# CONN.net
KiCad netlist of a schematic drawn in Altium Designer
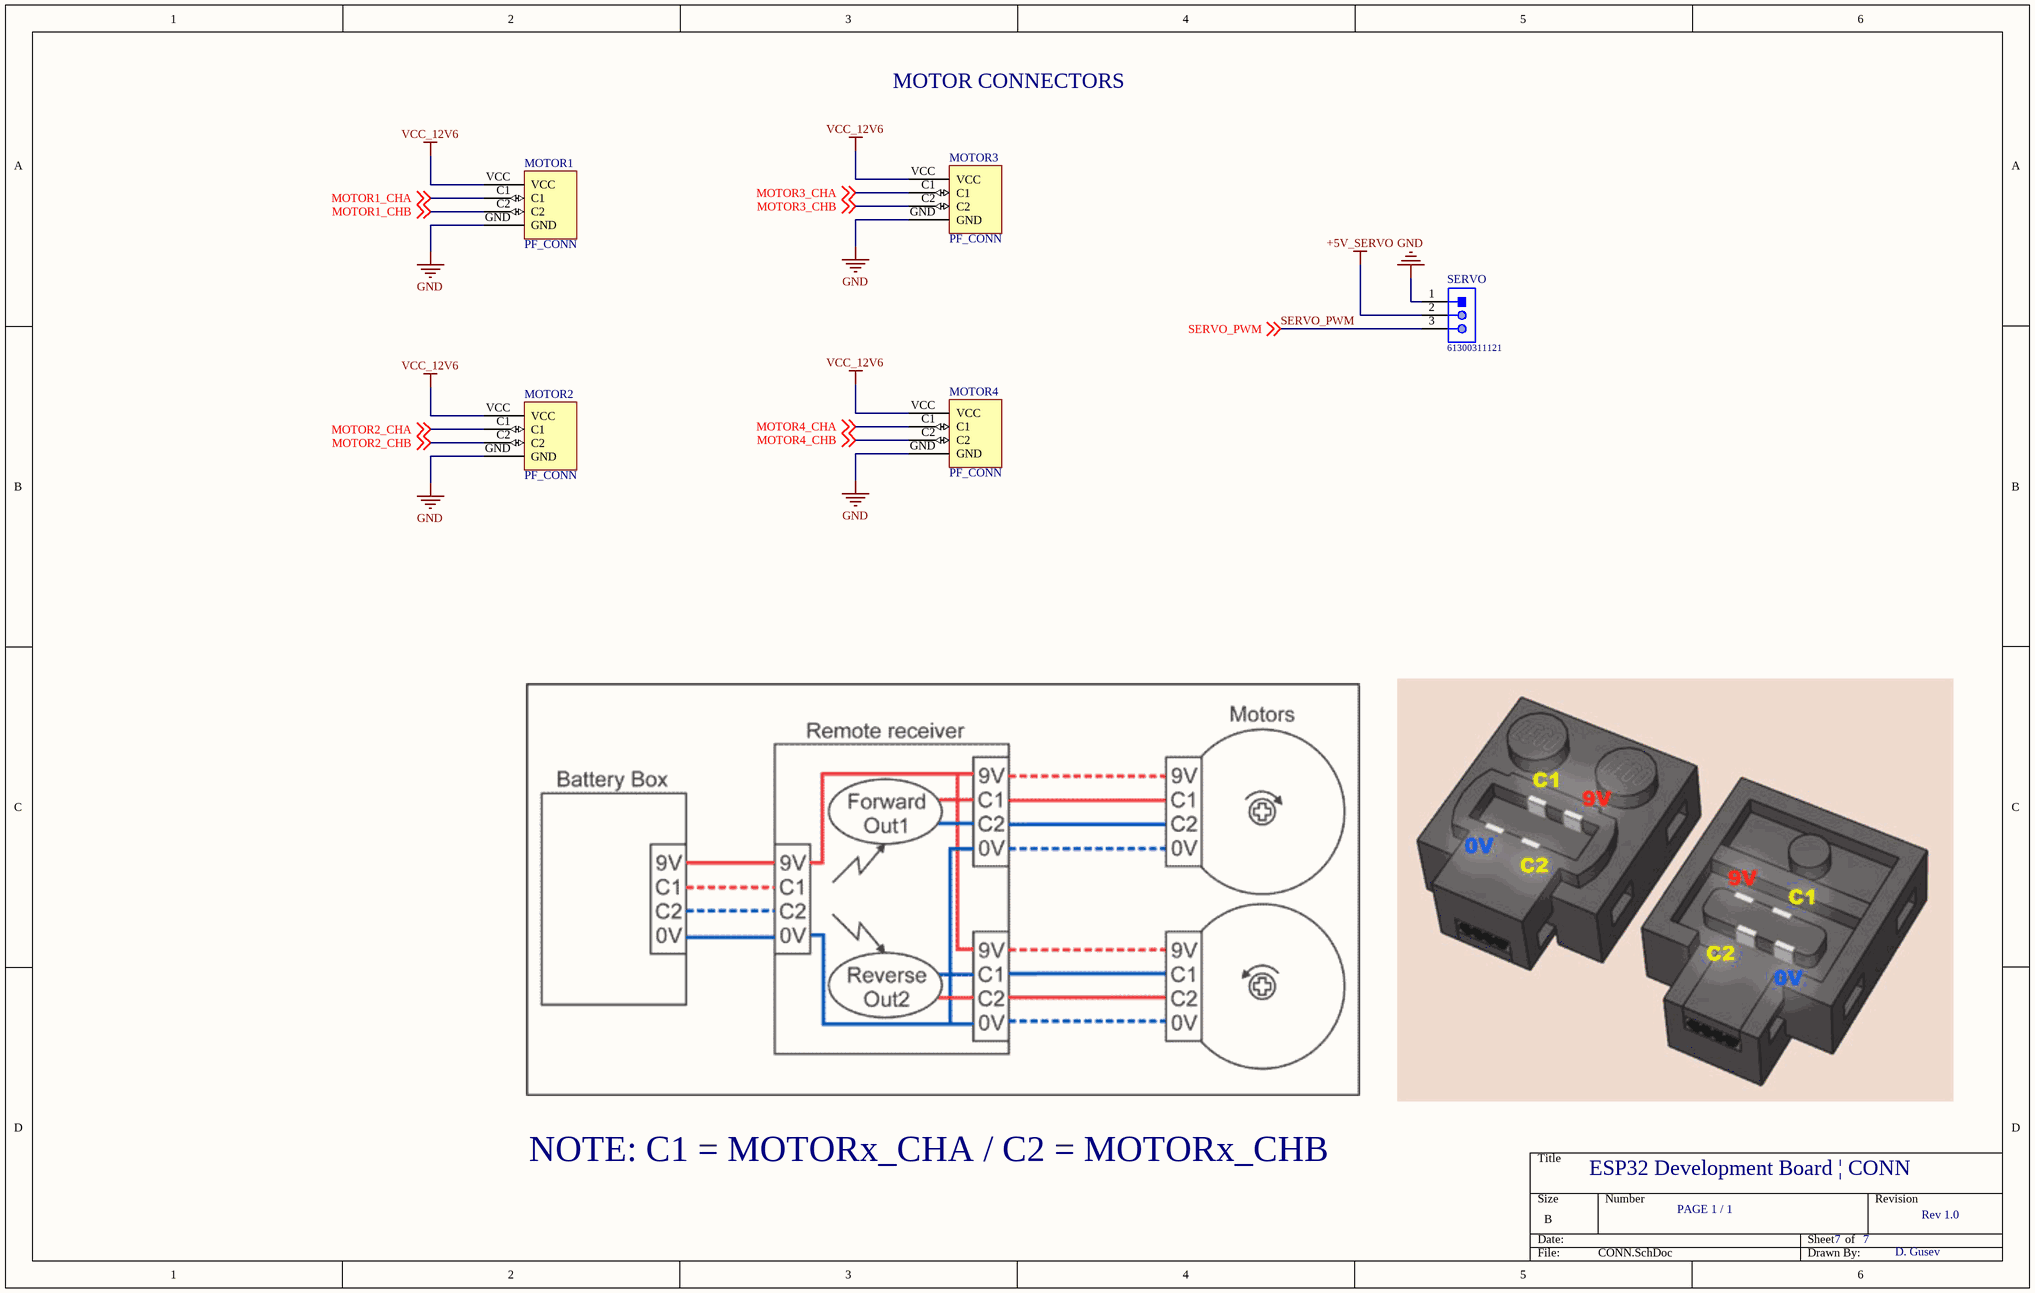
[diagram p0: CONN.SchDoc]

(export (version "E")
  (design (tool "Eeschema 10.0.6"))
  (components
    (comp (ref "MOTOR1")
      (value "PF_CONN")
      (footprint "PF_CONN")
      (libsource (lib "ddrlegobrick") (part "PF_CONN"))
    )
    (comp (ref "MOTOR2")
      (value "PF_CONN")
      (footprint "PF_CONN")
      (libsource (lib "ddrlegobrick") (part "PF_CONN"))
    )
    (comp (ref "MOTOR3")
      (value "PF_CONN")
      (footprint "PF_CONN")
      (libsource (lib "ddrlegobrick") (part "PF_CONN"))
    )
    (comp (ref "MOTOR4")
      (value "PF_CONN")
      (footprint "PF_CONN")
      (libsource (lib "ddrlegobrick") (part "PF_CONN"))
    )
    (comp (ref "SERVO")
      (value "61300311121")
      (footprint "61300311121")
      (description "THT Vertical Pin Header WR-PHD, Pitch 2.54 mm, Single Row, 3 pins")
      (fields (field (name "MANUFACTURER") "Wurth Elektronik") (field (name "PUBLISHER") "WurthElektronik"))
      (libsource (lib "Altium Content Vault") (part "WE-CN-1P-M-R3"))
    )
  )
  (nets
    (net (code "1") (name "+5V_SERVO") (class "Default")
      (node (ref "SERVO") (pin "2") (pinfunction "2_2") (pintype "passive"))
    )
    (net (code "2") (name "GND") (class "Default")
      (node (ref "MOTOR1") (pin "GND") (pinfunction "GND_GND") (pintype "power_in"))
      (node (ref "MOTOR2") (pin "GND") (pinfunction "GND_GND") (pintype "power_in"))
      (node (ref "MOTOR3") (pin "GND") (pinfunction "GND_GND") (pintype "power_in"))
      (node (ref "MOTOR4") (pin "GND") (pinfunction "GND_GND") (pintype "power_in"))
      (node (ref "SERVO") (pin "1") (pinfunction "1_1") (pintype "passive"))
    )
    (net (code "3") (name "MOTOR1_CHA") (class "Default")
      (node (ref "MOTOR1") (pin "C1") (pinfunction "C1_C1") (pintype "bidirectional"))
    )
    (net (code "4") (name "MOTOR1_CHB") (class "Default")
      (node (ref "MOTOR1") (pin "C2") (pinfunction "C2_C2") (pintype "bidirectional"))
    )
    (net (code "5") (name "MOTOR2_CHA") (class "Default")
      (node (ref "MOTOR2") (pin "C1") (pinfunction "C1_C1") (pintype "bidirectional"))
    )
    (net (code "6") (name "MOTOR2_CHB") (class "Default")
      (node (ref "MOTOR2") (pin "C2") (pinfunction "C2_C2") (pintype "bidirectional"))
    )
    (net (code "7") (name "MOTOR3_CHA") (class "Default")
      (node (ref "MOTOR3") (pin "C1") (pinfunction "C1_C1") (pintype "bidirectional"))
    )
    (net (code "8") (name "MOTOR3_CHB") (class "Default")
      (node (ref "MOTOR3") (pin "C2") (pinfunction "C2_C2") (pintype "bidirectional"))
    )
    (net (code "9") (name "MOTOR4_CHA") (class "Default")
      (node (ref "MOTOR4") (pin "C1") (pinfunction "C1_C1") (pintype "bidirectional"))
    )
    (net (code "10") (name "MOTOR4_CHB") (class "Default")
      (node (ref "MOTOR4") (pin "C2") (pinfunction "C2_C2") (pintype "bidirectional"))
    )
    (net (code "11") (name "SERVO_PWM") (class "Default")
      (node (ref "SERVO") (pin "3") (pinfunction "3_3") (pintype "passive"))
    )
    (net (code "12") (name "VCC_12V6") (class "Default")
      (node (ref "MOTOR1") (pin "VCC") (pinfunction "VCC_VCC") (pintype "power_in"))
      (node (ref "MOTOR2") (pin "VCC") (pinfunction "VCC_VCC") (pintype "power_in"))
      (node (ref "MOTOR3") (pin "VCC") (pinfunction "VCC_VCC") (pintype "power_in"))
      (node (ref "MOTOR4") (pin "VCC") (pinfunction "VCC_VCC") (pintype "power_in"))
    )
  )
)
